# SENSOR.net
KiCad netlist of a schematic drawn in Altium Designer
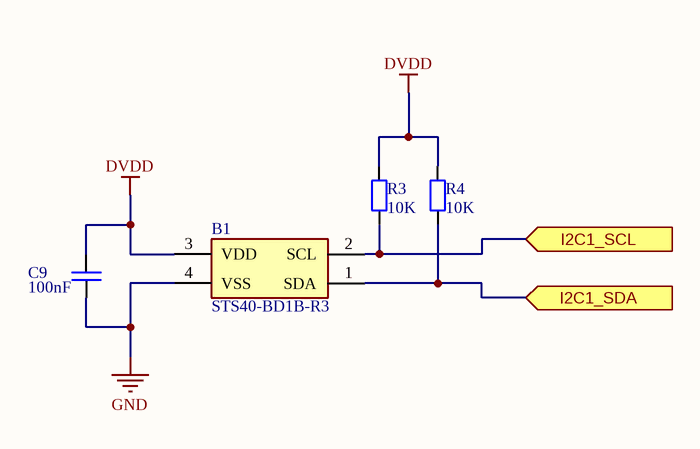
[diagram p0: SENSOR.SchDoc]

(export (version "E")
  (design (tool "Eeschema 10.0.6"))
  (components
    (comp (ref "B1")
      (value "STS40-BD1B-R3")
      (footprint "STS40BD1BR3")
      (description "Board Mount Temperature Sensors Base Accuracy Version, I2C Address 0x45")
      (libsource (lib "STS40-BD1B-R3") (part "STS40-BD1B-R3"))
    )
    (comp (ref "C9")
      (value "100nF")
      (footprint "CAP_SM0805_YAGEOCC2_N")
      (description "CAP 100nF SM0805 X7R 25V YAGEO CC2")
      (fields
        (field (name "MANUFACTURER") "Yageo")
        (field (name "MANUFACTURER PART NUMBER") "CC0805KRX7R8BB104")
      )
      (libsource (lib "Yageo") (part "CC0805KRX7R8BB104"))
    )
    (comp (ref "R3")
      (value "10K")
      (footprint "RES_SM0805_YAGEORC_N")
      (description "RES 10K SM0805 YAGEO RC_L")
      (fields
        (field (name "MANUFACTURER") "Yageo")
        (field (name "MANUFACTURER PART NUMBER") "RC0805FR-0710KL")
      )
      (libsource (lib "Yageo") (part "RC0805FR-0710KL"))
    )
    (comp (ref "R4")
      (value "10K")
      (footprint "RES_SM0805_YAGEORC_N")
      (description "RES 10K SM0805 YAGEO RC_L")
      (fields
        (field (name "MANUFACTURER") "Yageo")
        (field (name "MANUFACTURER PART NUMBER") "RC0805FR-0710KL")
      )
      (libsource (lib "Yageo") (part "RC0805FR-0710KL"))
    )
  )
  (nets
    (net (code "1") (name "/I2C1_SCL") (class "Default")
      (node (ref "B1") (pin "2") (pinfunction "SCL_2") (pintype "passive"))
      (node (ref "R3") (pin "1") (pintype "passive"))
    )
    (net (code "2") (name "/I2C1_SDA") (class "Default")
      (node (ref "B1") (pin "1") (pinfunction "SDA_1") (pintype "passive"))
      (node (ref "R4") (pin "1") (pintype "passive"))
    )
    (net (code "3") (name "DVDD") (class "Default")
      (node (ref "B1") (pin "3") (pinfunction "VDD_3") (pintype "passive"))
      (node (ref "C9") (pin "2") (pintype "passive"))
      (node (ref "R3") (pin "2") (pintype "passive"))
      (node (ref "R4") (pin "2") (pintype "passive"))
    )
    (net (code "4") (name "GND") (class "Default")
      (node (ref "B1") (pin "4") (pinfunction "VSS_4") (pintype "passive"))
      (node (ref "C9") (pin "1") (pintype "passive"))
    )
  )
)
